# cm5_redraw.net
KiCad netlist of a schematic drawn in EAGLE
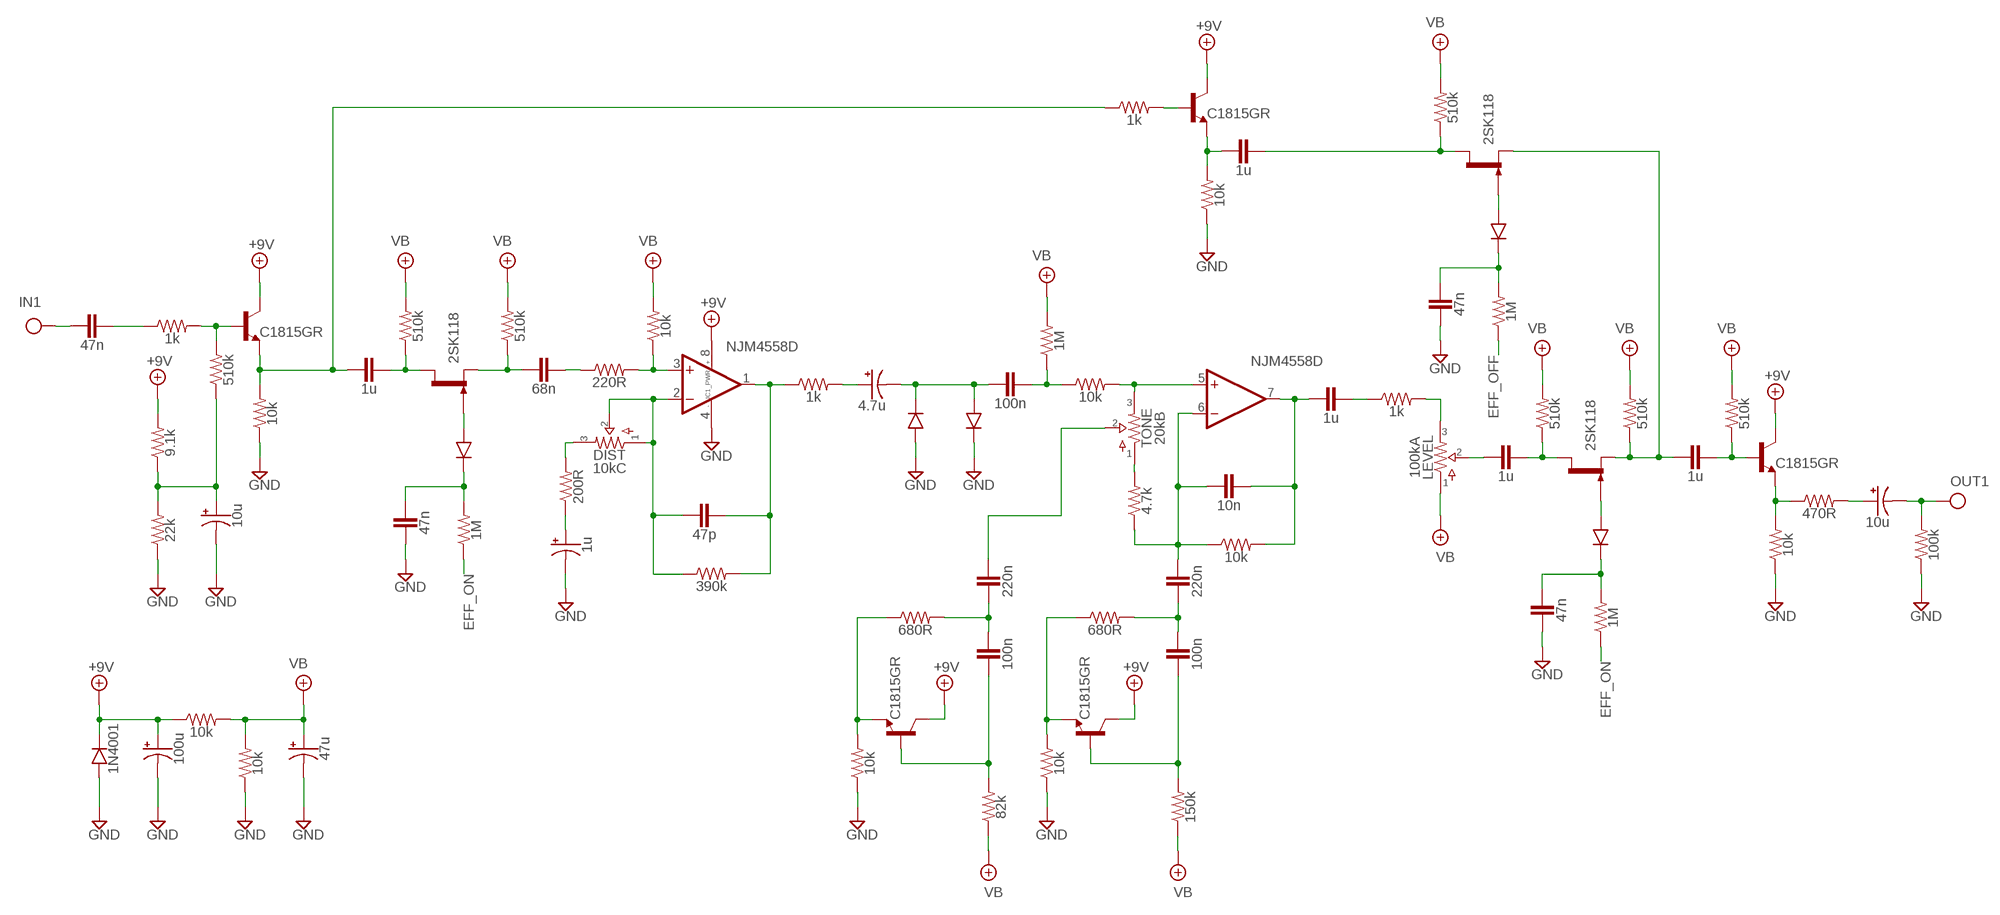
[diagram p0: schematic, sheet 1]

(export (version "E")
  (design (tool "Eeschema 10.0.6"))
  (components
    (comp (ref "C1")
      (value "47n")
      (footprint "eagle-import:050X030_025")
      (libsource (lib "eagle-import") (part "CER/FILM1"))
    )
    (comp (ref "C2")
      (value "10u")
      (footprint "eagle-import:050_020")
      (libsource (lib "eagle-import") (part "0500"))
    )
    (comp (ref "C3")
      (value "1u")
      (footprint "eagle-import:050X030_025")
      (libsource (lib "eagle-import") (part "CER/FILM1"))
    )
    (comp (ref "C4")
      (value "68n")
      (footprint "eagle-import:050X030_025")
      (libsource (lib "eagle-import") (part "CER/FILM1"))
    )
    (comp (ref "C5")
      (value "47p")
      (footprint "eagle-import:050X030_025")
      (libsource (lib "eagle-import") (part "CER/FILM1"))
    )
    (comp (ref "C6")
      (value "1u")
      (footprint "eagle-import:050_020")
      (libsource (lib "eagle-import") (part "0500"))
    )
    (comp (ref "C7")
      (value "4.7u")
      (footprint "eagle-import:050_020")
      (libsource (lib "eagle-import") (part "0500"))
    )
    (comp (ref "C8")
      (value "100n")
      (footprint "eagle-import:050X030_025")
      (libsource (lib "eagle-import") (part "CER/FILM1"))
    )
    (comp (ref "C9")
      (value "220n")
      (footprint "eagle-import:050X030_025")
      (libsource (lib "eagle-import") (part "CER/FILM1"))
    )
    (comp (ref "C10")
      (value "100n")
      (footprint "eagle-import:050X030_025")
      (libsource (lib "eagle-import") (part "CER/FILM1"))
    )
    (comp (ref "C11")
      (value "220n")
      (footprint "eagle-import:050X030_025")
      (libsource (lib "eagle-import") (part "CER/FILM1"))
    )
    (comp (ref "C12")
      (value "100n")
      (footprint "eagle-import:050X030_025")
      (libsource (lib "eagle-import") (part "CER/FILM1"))
    )
    (comp (ref "C15")
      (value "10n")
      (footprint "eagle-import:050X030_025")
      (libsource (lib "eagle-import") (part "CER/FILM1"))
    )
    (comp (ref "C16")
      (value "1u")
      (footprint "eagle-import:050X030_025")
      (libsource (lib "eagle-import") (part "CER/FILM1"))
    )
    (comp (ref "C17")
      (value "1u")
      (footprint "eagle-import:050X030_025")
      (libsource (lib "eagle-import") (part "CER/FILM1"))
    )
    (comp (ref "C18")
      (value "1u")
      (footprint "eagle-import:050X030_025")
      (libsource (lib "eagle-import") (part "CER/FILM1"))
    )
    (comp (ref "C19")
      (value "10u")
      (footprint "eagle-import:050_020")
      (libsource (lib "eagle-import") (part "0500"))
    )
    (comp (ref "C20")
      (value "1u")
      (footprint "eagle-import:050X030_025")
      (libsource (lib "eagle-import") (part "CER/FILM1"))
    )
    (comp (ref "C21")
      (value "47n")
      (footprint "eagle-import:050X030_025")
      (libsource (lib "eagle-import") (part "CER/FILM1"))
    )
    (comp (ref "C25")
      (value "47n")
      (footprint "eagle-import:050X030_025")
      (libsource (lib "eagle-import") (part "CER/FILM1"))
    )
    (comp (ref "C26")
      (value "47n")
      (footprint "eagle-import:050X030_025")
      (libsource (lib "eagle-import") (part "CER/FILM1"))
    )
    (comp (ref "C27")
      (value "100u")
      (footprint "eagle-import:050_020")
      (libsource (lib "eagle-import") (part "0500"))
    )
    (comp (ref "C28")
      (value "47u")
      (footprint "eagle-import:050_020")
      (libsource (lib "eagle-import") (part "0500"))
    )
    (comp (ref "D1")
      (value "1N4148")
      (footprint "eagle-import:DO41-2")
      (libsource (lib "eagle-import") (part "DO41.2"))
    )
    (comp (ref "D2")
      (value "1N4148")
      (footprint "eagle-import:DO41-2")
      (libsource (lib "eagle-import") (part "DO41.2"))
    )
    (comp (ref "D3")
      (value "1N4148")
      (footprint "eagle-import:DO41-2")
      (libsource (lib "eagle-import") (part "DO41.2"))
    )
    (comp (ref "D4")
      (value "1N4148")
      (footprint "eagle-import:DO41-2")
      (libsource (lib "eagle-import") (part "DO41.2"))
    )
    (comp (ref "D5")
      (value "1N4148")
      (footprint "eagle-import:DO41-2")
      (libsource (lib "eagle-import") (part "DO41.2"))
    )
    (comp (ref "D6")
      (value "1N4001")
      (footprint "eagle-import:DO41-2")
      (libsource (lib "eagle-import") (part "DO41.2"))
    )
    (comp (ref "DIST")
      (value "10kC")
      (footprint "eagle-import:16MM")
      (libsource (lib "eagle-import") (part "POTS16MM"))
    )
    (comp (ref "IC1")
      (value "NJM4558D")
      (footprint "eagle-import:DIL0")
      (libsource (lib "eagle-import") (part "DUALTH"))
    )
    (comp (ref "LEVEL")
      (value "100kA")
      (footprint "eagle-import:16MM")
      (libsource (lib "eagle-import") (part "POTS16MM"))
    )
    (comp (ref "Q1")
      (value "2SK118")
      (footprint "eagle-import:TO92-")
      (libsource (lib "eagle-import") (part "2SK170"))
    )
    (comp (ref "Q2")
      (value "2SK118")
      (footprint "eagle-import:TO92-")
      (libsource (lib "eagle-import") (part "2SK170"))
    )
    (comp (ref "Q3")
      (value "2SK118")
      (footprint "eagle-import:TO92-")
      (libsource (lib "eagle-import") (part "2SK170"))
    )
    (comp (ref "R1")
      (value "1k")
      (footprint "eagle-import:R0207_3")
      (libsource (lib "eagle-import") (part "R_.3B"))
    )
    (comp (ref "R2")
      (value "510k")
      (footprint "eagle-import:R0207_3")
      (libsource (lib "eagle-import") (part "R_.3B"))
    )
    (comp (ref "R3")
      (value "9.1k")
      (footprint "eagle-import:R0207_3")
      (libsource (lib "eagle-import") (part "R_.3B"))
    )
    (comp (ref "R4")
      (value "22k")
      (footprint "eagle-import:R0207_3")
      (libsource (lib "eagle-import") (part "R_.3B"))
    )
    (comp (ref "R5")
      (value "10k")
      (footprint "eagle-import:R0207_3")
      (libsource (lib "eagle-import") (part "R_.3B"))
    )
    (comp (ref "R6")
      (value "510k")
      (footprint "eagle-import:R0207_3")
      (libsource (lib "eagle-import") (part "R_.3B"))
    )
    (comp (ref "R7")
      (value "510k")
      (footprint "eagle-import:R0207_3")
      (libsource (lib "eagle-import") (part "R_.3B"))
    )
    (comp (ref "R8")
      (value "220R")
      (footprint "eagle-import:R0207_3")
      (libsource (lib "eagle-import") (part "R_.3B"))
    )
    (comp (ref "R9")
      (value "10k")
      (footprint "eagle-import:R0207_3")
      (libsource (lib "eagle-import") (part "R_.3B"))
    )
    (comp (ref "R10")
      (value "390k")
      (footprint "eagle-import:R0207_3")
      (libsource (lib "eagle-import") (part "R_.3B"))
    )
    (comp (ref "R11")
      (value "200R")
      (footprint "eagle-import:R0207_3")
      (libsource (lib "eagle-import") (part "R_.3B"))
    )
    (comp (ref "R12")
      (value "1k")
      (footprint "eagle-import:R0207_3")
      (libsource (lib "eagle-import") (part "R_.3B"))
    )
    (comp (ref "R13")
      (value "1M")
      (footprint "eagle-import:R0207_3")
      (libsource (lib "eagle-import") (part "R_.3B"))
    )
    (comp (ref "R14")
      (value "10k")
      (footprint "eagle-import:R0207_3")
      (libsource (lib "eagle-import") (part "R_.3B"))
    )
    (comp (ref "R15")
      (value "680R")
      (footprint "eagle-import:R0207_3")
      (libsource (lib "eagle-import") (part "R_.3B"))
    )
    (comp (ref "R16")
      (value "10k")
      (footprint "eagle-import:R0207_3")
      (libsource (lib "eagle-import") (part "R_.3B"))
    )
    (comp (ref "R17")
      (value "82k")
      (footprint "eagle-import:R0207_3")
      (libsource (lib "eagle-import") (part "R_.3B"))
    )
    (comp (ref "R18")
      (value "4.7k")
      (footprint "eagle-import:R0207_3")
      (libsource (lib "eagle-import") (part "R_.3B"))
    )
    (comp (ref "R19")
      (value "680R")
      (footprint "eagle-import:R0207_3")
      (libsource (lib "eagle-import") (part "R_.3B"))
    )
    (comp (ref "R20")
      (value "10k")
      (footprint "eagle-import:R0207_3")
      (libsource (lib "eagle-import") (part "R_.3B"))
    )
    (comp (ref "R21")
      (value "150k")
      (footprint "eagle-import:R0207_3")
      (libsource (lib "eagle-import") (part "R_.3B"))
    )
    (comp (ref "R25")
      (value "10k")
      (footprint "eagle-import:R0207_3")
      (libsource (lib "eagle-import") (part "R_.3B"))
    )
    (comp (ref "R26")
      (value "1k")
      (footprint "eagle-import:R0207_3")
      (libsource (lib "eagle-import") (part "R_.3B"))
    )
    (comp (ref "R27")
      (value "510k")
      (footprint "eagle-import:R0207_3")
      (libsource (lib "eagle-import") (part "R_.3B"))
    )
    (comp (ref "R28")
      (value "510k")
      (footprint "eagle-import:R0207_3")
      (libsource (lib "eagle-import") (part "R_.3B"))
    )
    (comp (ref "R29")
      (value "10k")
      (footprint "eagle-import:R0207_3")
      (libsource (lib "eagle-import") (part "R_.3B"))
    )
    (comp (ref "R30")
      (value "470R")
      (footprint "eagle-import:R0207_3")
      (libsource (lib "eagle-import") (part "R_.3B"))
    )
    (comp (ref "R31")
      (value "100k")
      (footprint "eagle-import:R0207_3")
      (libsource (lib "eagle-import") (part "R_.3B"))
    )
    (comp (ref "R32")
      (value "1k")
      (footprint "eagle-import:R0207_3")
      (libsource (lib "eagle-import") (part "R_.3B"))
    )
    (comp (ref "R33")
      (value "10k")
      (footprint "eagle-import:R0207_3")
      (libsource (lib "eagle-import") (part "R_.3B"))
    )
    (comp (ref "R34")
      (value "510k")
      (footprint "eagle-import:R0207_3")
      (libsource (lib "eagle-import") (part "R_.3B"))
    )
    (comp (ref "R35")
      (value "510k")
      (footprint "eagle-import:R0207_3")
      (libsource (lib "eagle-import") (part "R_.3B"))
    )
    (comp (ref "R36")
      (value "1M")
      (footprint "eagle-import:R0207_3")
      (libsource (lib "eagle-import") (part "R_.3B"))
    )
    (comp (ref "R40")
      (value "10k")
      (footprint "eagle-import:R0207_3")
      (libsource (lib "eagle-import") (part "R_.3B"))
    )
    (comp (ref "R44")
      (value "1M")
      (footprint "eagle-import:R0207_3")
      (libsource (lib "eagle-import") (part "R_.3B"))
    )
    (comp (ref "R45")
      (value "1M")
      (footprint "eagle-import:R0207_3")
      (libsource (lib "eagle-import") (part "R_.3B"))
    )
    (comp (ref "R49")
      (value "10k")
      (footprint "eagle-import:R0207_3")
      (libsource (lib "eagle-import") (part "R_.3B"))
    )
    (comp (ref "TONE")
      (value "20kB")
      (footprint "eagle-import:16MM")
      (libsource (lib "eagle-import") (part "POTS16MM"))
    )
    (comp (ref "TR1")
      (value "C1815GR")
      (footprint "eagle-import:TO92-")
      (libsource (lib "eagle-import") (part "2N3904"))
    )
    (comp (ref "TR2")
      (value "C1815GR")
      (footprint "eagle-import:TO92-")
      (libsource (lib "eagle-import") (part "2N3904"))
    )
    (comp (ref "TR3")
      (value "C1815GR")
      (footprint "eagle-import:TO92-")
      (libsource (lib "eagle-import") (part "2N3904"))
    )
    (comp (ref "TR5")
      (value "C1815GR")
      (footprint "eagle-import:TO92-")
      (libsource (lib "eagle-import") (part "2N3904"))
    )
    (comp (ref "TR6")
      (value "C1815GR")
      (footprint "eagle-import:TO92-")
      (libsource (lib "eagle-import") (part "2N3904"))
    )
  )
  (nets
    (net (code "1") (name "+9V") (class "Default")
      (node (ref "C27") (pin "+") (pinfunction "+_+") (pintype "passive"))
      (node (ref "D6") (pin "C") (pinfunction "C_C") (pintype "passive"))
      (node (ref "IC1") (pin "8") (pinfunction "V+_8") (pintype "power_in"))
      (node (ref "R3") (pin "2") (pinfunction "2_2") (pintype "passive"))
      (node (ref "R40") (pin "1") (pinfunction "1_1") (pintype "passive"))
      (node (ref "TR1") (pin "1") (pinfunction "C_1") (pintype "passive"))
      (node (ref "TR2") (pin "1") (pinfunction "C_1") (pintype "passive"))
      (node (ref "TR3") (pin "1") (pinfunction "C_1") (pintype "passive"))
      (node (ref "TR5") (pin "1") (pinfunction "C_1") (pintype "passive"))
      (node (ref "TR6") (pin "1") (pinfunction "C_1") (pintype "passive"))
    )
    (net (code "2") (name "/EFF_OFF") (class "Default")
      (node (ref "R36") (pin "1") (pinfunction "1_1") (pintype "passive"))
    )
    (net (code "3") (name "/EFF_ON") (class "Default")
      (node (ref "R44") (pin "1") (pinfunction "1_1") (pintype "passive"))
    )
    (net (code "4") (name "GND") (class "Default")
      (node (ref "C2") (pin "-") (pinfunction "-_-") (pintype "passive"))
      (node (ref "C21") (pin "2") (pinfunction "2_2") (pintype "passive"))
      (node (ref "C25") (pin "2") (pinfunction "2_2") (pintype "passive"))
      (node (ref "C26") (pin "2") (pinfunction "2_2") (pintype "passive"))
      (node (ref "C27") (pin "-") (pinfunction "-_-") (pintype "passive"))
      (node (ref "C28") (pin "-") (pinfunction "-_-") (pintype "passive"))
      (node (ref "C6") (pin "-") (pinfunction "-_-") (pintype "passive"))
      (node (ref "D2") (pin "C") (pinfunction "C_C") (pintype "passive"))
      (node (ref "D3") (pin "A") (pinfunction "A_A") (pintype "passive"))
      (node (ref "D6") (pin "A") (pinfunction "A_A") (pintype "passive"))
      (node (ref "IC1") (pin "4") (pinfunction "V-_4") (pintype "power_in"))
      (node (ref "R16") (pin "1") (pinfunction "1_1") (pintype "passive"))
      (node (ref "R20") (pin "1") (pinfunction "1_1") (pintype "passive"))
      (node (ref "R29") (pin "1") (pinfunction "1_1") (pintype "passive"))
      (node (ref "R31") (pin "1") (pinfunction "1_1") (pintype "passive"))
      (node (ref "R33") (pin "1") (pinfunction "1_1") (pintype "passive"))
      (node (ref "R4") (pin "1") (pinfunction "1_1") (pintype "passive"))
      (node (ref "R49") (pin "1") (pinfunction "1_1") (pintype "passive"))
      (node (ref "R5") (pin "1") (pinfunction "1_1") (pintype "passive"))
    )
    (net (code "5") (name "IN") (class "Default")
      (node (ref "C1") (pin "2") (pinfunction "2_2") (pintype "passive"))
    )
    (net (code "6") (name "Net-(C1-Pad1)") (class "Default")
      (node (ref "C1") (pin "1") (pinfunction "1_1") (pintype "passive"))
      (node (ref "R1") (pin "1") (pinfunction "1_1") (pintype "passive"))
    )
    (net (code "7") (name "Net-(C2-Pad+)") (class "Default")
      (node (ref "C2") (pin "+") (pinfunction "+_+") (pintype "passive"))
      (node (ref "R2") (pin "1") (pinfunction "1_1") (pintype "passive"))
      (node (ref "R3") (pin "1") (pinfunction "1_1") (pintype "passive"))
      (node (ref "R4") (pin "2") (pinfunction "2_2") (pintype "passive"))
    )
    (net (code "8") (name "Net-(C4-Pad1)") (class "Default")
      (node (ref "C4") (pin "1") (pinfunction "1_1") (pintype "passive"))
      (node (ref "R8") (pin "1") (pinfunction "1_1") (pintype "passive"))
    )
    (net (code "9") (name "Net-(C6-Pad+)") (class "Default")
      (node (ref "C6") (pin "+") (pinfunction "+_+") (pintype "passive"))
      (node (ref "R11") (pin "1") (pinfunction "1_1") (pintype "passive"))
    )
    (net (code "10") (name "Net-(C7-Pad+)") (class "Default")
      (node (ref "C7") (pin "+") (pinfunction "+_+") (pintype "passive"))
      (node (ref "R12") (pin "2") (pinfunction "2_2") (pintype "passive"))
    )
    (net (code "11") (name "Net-(C7-Pad-)") (class "Default")
      (node (ref "C7") (pin "-") (pinfunction "-_-") (pintype "passive"))
      (node (ref "C8") (pin "2") (pinfunction "2_2") (pintype "passive"))
      (node (ref "D2") (pin "A") (pinfunction "A_A") (pintype "passive"))
      (node (ref "D3") (pin "C") (pinfunction "C_C") (pintype "passive"))
    )
    (net (code "12") (name "Net-(C8-Pad1)") (class "Default")
      (node (ref "C8") (pin "1") (pinfunction "1_1") (pintype "passive"))
      (node (ref "R13") (pin "1") (pinfunction "1_1") (pintype "passive"))
      (node (ref "R14") (pin "1") (pinfunction "1_1") (pintype "passive"))
    )
    (net (code "13") (name "Net-(C9-Pad1)") (class "Default")
      (node (ref "C9") (pin "1") (pinfunction "1_1") (pintype "passive"))
      (node (ref "TONE") (pin "2") (pinfunction "2_2") (pintype "passive"))
    )
    (net (code "14") (name "Net-(C10-Pad1)") (class "Default")
      (node (ref "C10") (pin "1") (pinfunction "1_1") (pintype "passive"))
      (node (ref "C9") (pin "2") (pinfunction "2_2") (pintype "passive"))
      (node (ref "R15") (pin "2") (pinfunction "2_2") (pintype "passive"))
    )
    (net (code "15") (name "Net-(C11-Pad2)") (class "Default")
      (node (ref "C11") (pin "2") (pinfunction "2_2") (pintype "passive"))
      (node (ref "C12") (pin "1") (pinfunction "1_1") (pintype "passive"))
      (node (ref "R19") (pin "2") (pinfunction "2_2") (pintype "passive"))
    )
    (net (code "16") (name "Net-(C16-Pad1)") (class "Default")
      (node (ref "C16") (pin "1") (pinfunction "1_1") (pintype "passive"))
      (node (ref "R26") (pin "1") (pinfunction "1_1") (pintype "passive"))
    )
    (net (code "17") (name "Net-(C17-Pad2)") (class "Default")
      (node (ref "C17") (pin "2") (pinfunction "2_2") (pintype "passive"))
      (node (ref "LEVEL") (pin "2") (pinfunction "2_2") (pintype "passive"))
    )
    (net (code "18") (name "Net-(C19-Pad+)") (class "Default")
      (node (ref "C19") (pin "+") (pinfunction "+_+") (pintype "passive"))
      (node (ref "R30") (pin "2") (pinfunction "2_2") (pintype "passive"))
    )
    (net (code "19") (name "Net-(C21-Pad1)") (class "Default")
      (node (ref "C21") (pin "1") (pinfunction "1_1") (pintype "passive"))
      (node (ref "D5") (pin "C") (pinfunction "C_C") (pintype "passive"))
      (node (ref "R36") (pin "2") (pinfunction "2_2") (pintype "passive"))
    )
    (net (code "20") (name "Net-(C25-Pad1)") (class "Default")
      (node (ref "C25") (pin "1") (pinfunction "1_1") (pintype "passive"))
      (node (ref "D1") (pin "C") (pinfunction "C_C") (pintype "passive"))
      (node (ref "R44") (pin "2") (pinfunction "2_2") (pintype "passive"))
    )
    (net (code "21") (name "Net-(C26-Pad1)") (class "Default")
      (node (ref "C26") (pin "1") (pinfunction "1_1") (pintype "passive"))
      (node (ref "D4") (pin "C") (pinfunction "C_C") (pintype "passive"))
      (node (ref "R45") (pin "2") (pinfunction "2_2") (pintype "passive"))
    )
    (net (code "22") (name "Net-(DIST-Pad3)") (class "Default")
      (node (ref "DIST") (pin "3") (pinfunction "3_3") (pintype "passive"))
      (node (ref "R11") (pin "2") (pinfunction "2_2") (pintype "passive"))
    )
    (net (code "23") (name "Net-(IC1A-+IN)") (class "Default")
      (node (ref "IC1") (pin "3") (pinfunction "+IN_3") (pintype "input"))
      (node (ref "R8") (pin "2") (pinfunction "2_2") (pintype "passive"))
      (node (ref "R9") (pin "1") (pinfunction "1_1") (pintype "passive"))
    )
    (net (code "24") (name "Net-(IC1A--IN)") (class "Default")
      (node (ref "C5") (pin "2") (pinfunction "2_2") (pintype "passive"))
      (node (ref "DIST") (pin "1") (pinfunction "1_1") (pintype "passive"))
      (node (ref "DIST") (pin "2") (pinfunction "2_2") (pintype "passive"))
      (node (ref "IC1") (pin "2") (pinfunction "-IN_2") (pintype "input"))
      (node (ref "R10") (pin "1") (pinfunction "1_1") (pintype "passive"))
    )
    (net (code "25") (name "Net-(IC1A-OUT)") (class "Default")
      (node (ref "C5") (pin "1") (pinfunction "1_1") (pintype "passive"))
      (node (ref "IC1") (pin "1") (pinfunction "OUT_1") (pintype "output"))
      (node (ref "R10") (pin "2") (pinfunction "2_2") (pintype "passive"))
      (node (ref "R12") (pin "1") (pinfunction "1_1") (pintype "passive"))
    )
    (net (code "26") (name "Net-(IC1B-+IN)") (class "Default")
      (node (ref "IC1") (pin "5") (pinfunction "+IN_5") (pintype "input"))
      (node (ref "R14") (pin "2") (pinfunction "2_2") (pintype "passive"))
      (node (ref "TONE") (pin "3") (pinfunction "3_3") (pintype "passive"))
    )
    (net (code "27") (name "Net-(IC1B--IN)") (class "Default")
      (node (ref "C11") (pin "1") (pinfunction "1_1") (pintype "passive"))
      (node (ref "C15") (pin "2") (pinfunction "2_2") (pintype "passive"))
      (node (ref "IC1") (pin "6") (pinfunction "-IN_6") (pintype "input"))
      (node (ref "R18") (pin "1") (pinfunction "1_1") (pintype "passive"))
      (node (ref "R25") (pin "1") (pinfunction "1_1") (pintype "passive"))
    )
    (net (code "28") (name "Net-(IC1B-OUT)") (class "Default")
      (node (ref "C15") (pin "1") (pinfunction "1_1") (pintype "passive"))
      (node (ref "C16") (pin "2") (pinfunction "2_2") (pintype "passive"))
      (node (ref "IC1") (pin "7") (pinfunction "OUT_7") (pintype "output"))
      (node (ref "R25") (pin "2") (pinfunction "2_2") (pintype "passive"))
    )
    (net (code "29") (name "Net-(LEVEL-Pad3)") (class "Default")
      (node (ref "LEVEL") (pin "3") (pinfunction "3_3") (pintype "passive"))
      (node (ref "R26") (pin "2") (pinfunction "2_2") (pintype "passive"))
    )
    (net (code "30") (name "Net-(Q1-D)") (class "Default")
      (node (ref "C3") (pin "1") (pinfunction "1_1") (pintype "passive"))
      (node (ref "Q1") (pin "3") (pinfunction "D_3") (pintype "passive"))
      (node (ref "R6") (pin "1") (pinfunction "1_1") (pintype "passive"))
    )
    (net (code "31") (name "Net-(Q1-G)") (class "Default")
      (node (ref "D1") (pin "A") (pinfunction "A_A") (pintype "passive"))
      (node (ref "Q1") (pin "2") (pinfunction "G_2") (pintype "passive"))
    )
    (net (code "32") (name "Net-(Q1-S)") (class "Default")
      (node (ref "C4") (pin "2") (pinfunction "2_2") (pintype "passive"))
      (node (ref "Q1") (pin "1") (pinfunction "S_1") (pintype "passive"))
      (node (ref "R7") (pin "1") (pinfunction "1_1") (pintype "passive"))
    )
    (net (code "33") (name "Net-(Q2-D)") (class "Default")
      (node (ref "C17") (pin "1") (pinfunction "1_1") (pintype "passive"))
      (node (ref "Q2") (pin "3") (pinfunction "D_3") (pintype "passive"))
      (node (ref "R27") (pin "1") (pinfunction "1_1") (pintype "passive"))
    )
    (net (code "34") (name "Net-(Q2-G)") (class "Default")
      (node (ref "D4") (pin "A") (pinfunction "A_A") (pintype "passive"))
      (node (ref "Q2") (pin "2") (pinfunction "G_2") (pintype "passive"))
    )
    (net (code "35") (name "Net-(Q2-S)") (class "Default")
      (node (ref "C18") (pin "2") (pinfunction "2_2") (pintype "passive"))
      (node (ref "Q2") (pin "1") (pinfunction "S_1") (pintype "passive"))
      (node (ref "Q3") (pin "1") (pinfunction "S_1") (pintype "passive"))
      (node (ref "R35") (pin "1") (pinfunction "1_1") (pintype "passive"))
    )
    (net (code "36") (name "Net-(Q3-D)") (class "Default")
      (node (ref "C20") (pin "1") (pinfunction "1_1") (pintype "passive"))
      (node (ref "Q3") (pin "3") (pinfunction "D_3") (pintype "passive"))
      (node (ref "R34") (pin "1") (pinfunction "1_1") (pintype "passive"))
    )
    (net (code "37") (name "Net-(Q3-G)") (class "Default")
      (node (ref "D5") (pin "A") (pinfunction "A_A") (pintype "passive"))
      (node (ref "Q3") (pin "2") (pinfunction "G_2") (pintype "passive"))
    )
    (net (code "38") (name "Net-(R18-Pad2)") (class "Default")
      (node (ref "R18") (pin "2") (pinfunction "2_2") (pintype "passive"))
      (node (ref "TONE") (pin "1") (pinfunction "1_1") (pintype "passive"))
    )
    (net (code "39") (name "Net-(TR1-B)") (class "Default")
      (node (ref "R1") (pin "2") (pinfunction "2_2") (pintype "passive"))
      (node (ref "R2") (pin "2") (pinfunction "2_2") (pintype "passive"))
      (node (ref "TR1") (pin "2") (pinfunction "B_2") (pintype "passive"))
    )
    (net (code "40") (name "Net-(TR1-E)") (class "Default")
      (node (ref "C3") (pin "2") (pinfunction "2_2") (pintype "passive"))
      (node (ref "R32") (pin "1") (pinfunction "1_1") (pintype "passive"))
      (node (ref "R5") (pin "2") (pinfunction "2_2") (pintype "passive"))
      (node (ref "TR1") (pin "3") (pinfunction "E_3") (pintype "passive"))
    )
    (net (code "41") (name "Net-(TR2-B)") (class "Default")
      (node (ref "C10") (pin "2") (pinfunction "2_2") (pintype "passive"))
      (node (ref "R17") (pin "2") (pinfunction "2_2") (pintype "passive"))
      (node (ref "TR2") (pin "2") (pinfunction "B_2") (pintype "passive"))
    )
    (net (code "42") (name "Net-(TR2-E)") (class "Default")
      (node (ref "R15") (pin "1") (pinfunction "1_1") (pintype "passive"))
      (node (ref "R16") (pin "2") (pinfunction "2_2") (pintype "passive"))
      (node (ref "TR2") (pin "3") (pinfunction "E_3") (pintype "passive"))
    )
    (net (code "43") (name "Net-(TR3-B)") (class "Default")
      (node (ref "C12") (pin "2") (pinfunction "2_2") (pintype "passive"))
      (node (ref "R21") (pin "2") (pinfunction "2_2") (pintype "passive"))
      (node (ref "TR3") (pin "2") (pinfunction "B_2") (pintype "passive"))
    )
    (net (code "44") (name "Net-(TR3-E)") (class "Default")
      (node (ref "R19") (pin "1") (pinfunction "1_1") (pintype "passive"))
      (node (ref "R20") (pin "2") (pinfunction "2_2") (pintype "passive"))
      (node (ref "TR3") (pin "3") (pinfunction "E_3") (pintype "passive"))
    )
    (net (code "45") (name "Net-(TR5-B)") (class "Default")
      (node (ref "C18") (pin "1") (pinfunction "1_1") (pintype "passive"))
      (node (ref "R28") (pin "1") (pinfunction "1_1") (pintype "passive"))
      (node (ref "TR5") (pin "2") (pinfunction "B_2") (pintype "passive"))
    )
    (net (code "46") (name "Net-(TR5-E)") (class "Default")
      (node (ref "R29") (pin "2") (pinfunction "2_2") (pintype "passive"))
      (node (ref "R30") (pin "1") (pinfunction "1_1") (pintype "passive"))
      (node (ref "TR5") (pin "3") (pinfunction "E_3") (pintype "passive"))
    )
    (net (code "47") (name "Net-(TR6-B)") (class "Default")
      (node (ref "R32") (pin "2") (pinfunction "2_2") (pintype "passive"))
      (node (ref "TR6") (pin "2") (pinfunction "B_2") (pintype "passive"))
    )
    (net (code "48") (name "Net-(TR6-E)") (class "Default")
      (node (ref "C20") (pin "2") (pinfunction "2_2") (pintype "passive"))
      (node (ref "R33") (pin "2") (pinfunction "2_2") (pintype "passive"))
      (node (ref "TR6") (pin "3") (pinfunction "E_3") (pintype "passive"))
    )
    (net (code "49") (name "OUT") (class "Default")
      (node (ref "C19") (pin "-") (pinfunction "-_-") (pintype "passive"))
      (node (ref "R31") (pin "2") (pinfunction "2_2") (pintype "passive"))
    )
    (net (code "50") (name "VB") (class "Default")
      (node (ref "C28") (pin "+") (pinfunction "+_+") (pintype "passive"))
      (node (ref "LEVEL") (pin "1") (pinfunction "1_1") (pintype "passive"))
      (node (ref "R13") (pin "2") (pinfunction "2_2") (pintype "passive"))
      (node (ref "R17") (pin "1") (pinfunction "1_1") (pintype "passive"))
      (node (ref "R21") (pin "1") (pinfunction "1_1") (pintype "passive"))
      (node (ref "R27") (pin "2") (pinfunction "2_2") (pintype "passive"))
      (node (ref "R28") (pin "2") (pinfunction "2_2") (pintype "passive"))
      (node (ref "R34") (pin "2") (pinfunction "2_2") (pintype "passive"))
      (node (ref "R35") (pin "2") (pinfunction "2_2") (pintype "passive"))
      (node (ref "R40") (pin "2") (pinfunction "2_2") (pintype "passive"))
      (node (ref "R49") (pin "2") (pinfunction "2_2") (pintype "passive"))
      (node (ref "R6") (pin "2") (pinfunction "2_2") (pintype "passive"))
      (node (ref "R7") (pin "2") (pinfunction "2_2") (pintype "passive"))
      (node (ref "R9") (pin "2") (pinfunction "2_2") (pintype "passive"))
    )
    (net (code "51") (name "unconnected-(R45-Pad1)") (class "Default")
      (node (ref "R45") (pin "1") (pinfunction "1_1") (pintype "passive"))
    )
  )
)
